# SCH_FinalThesis.net
KiCad netlist of a schematic drawn in EasyEDA
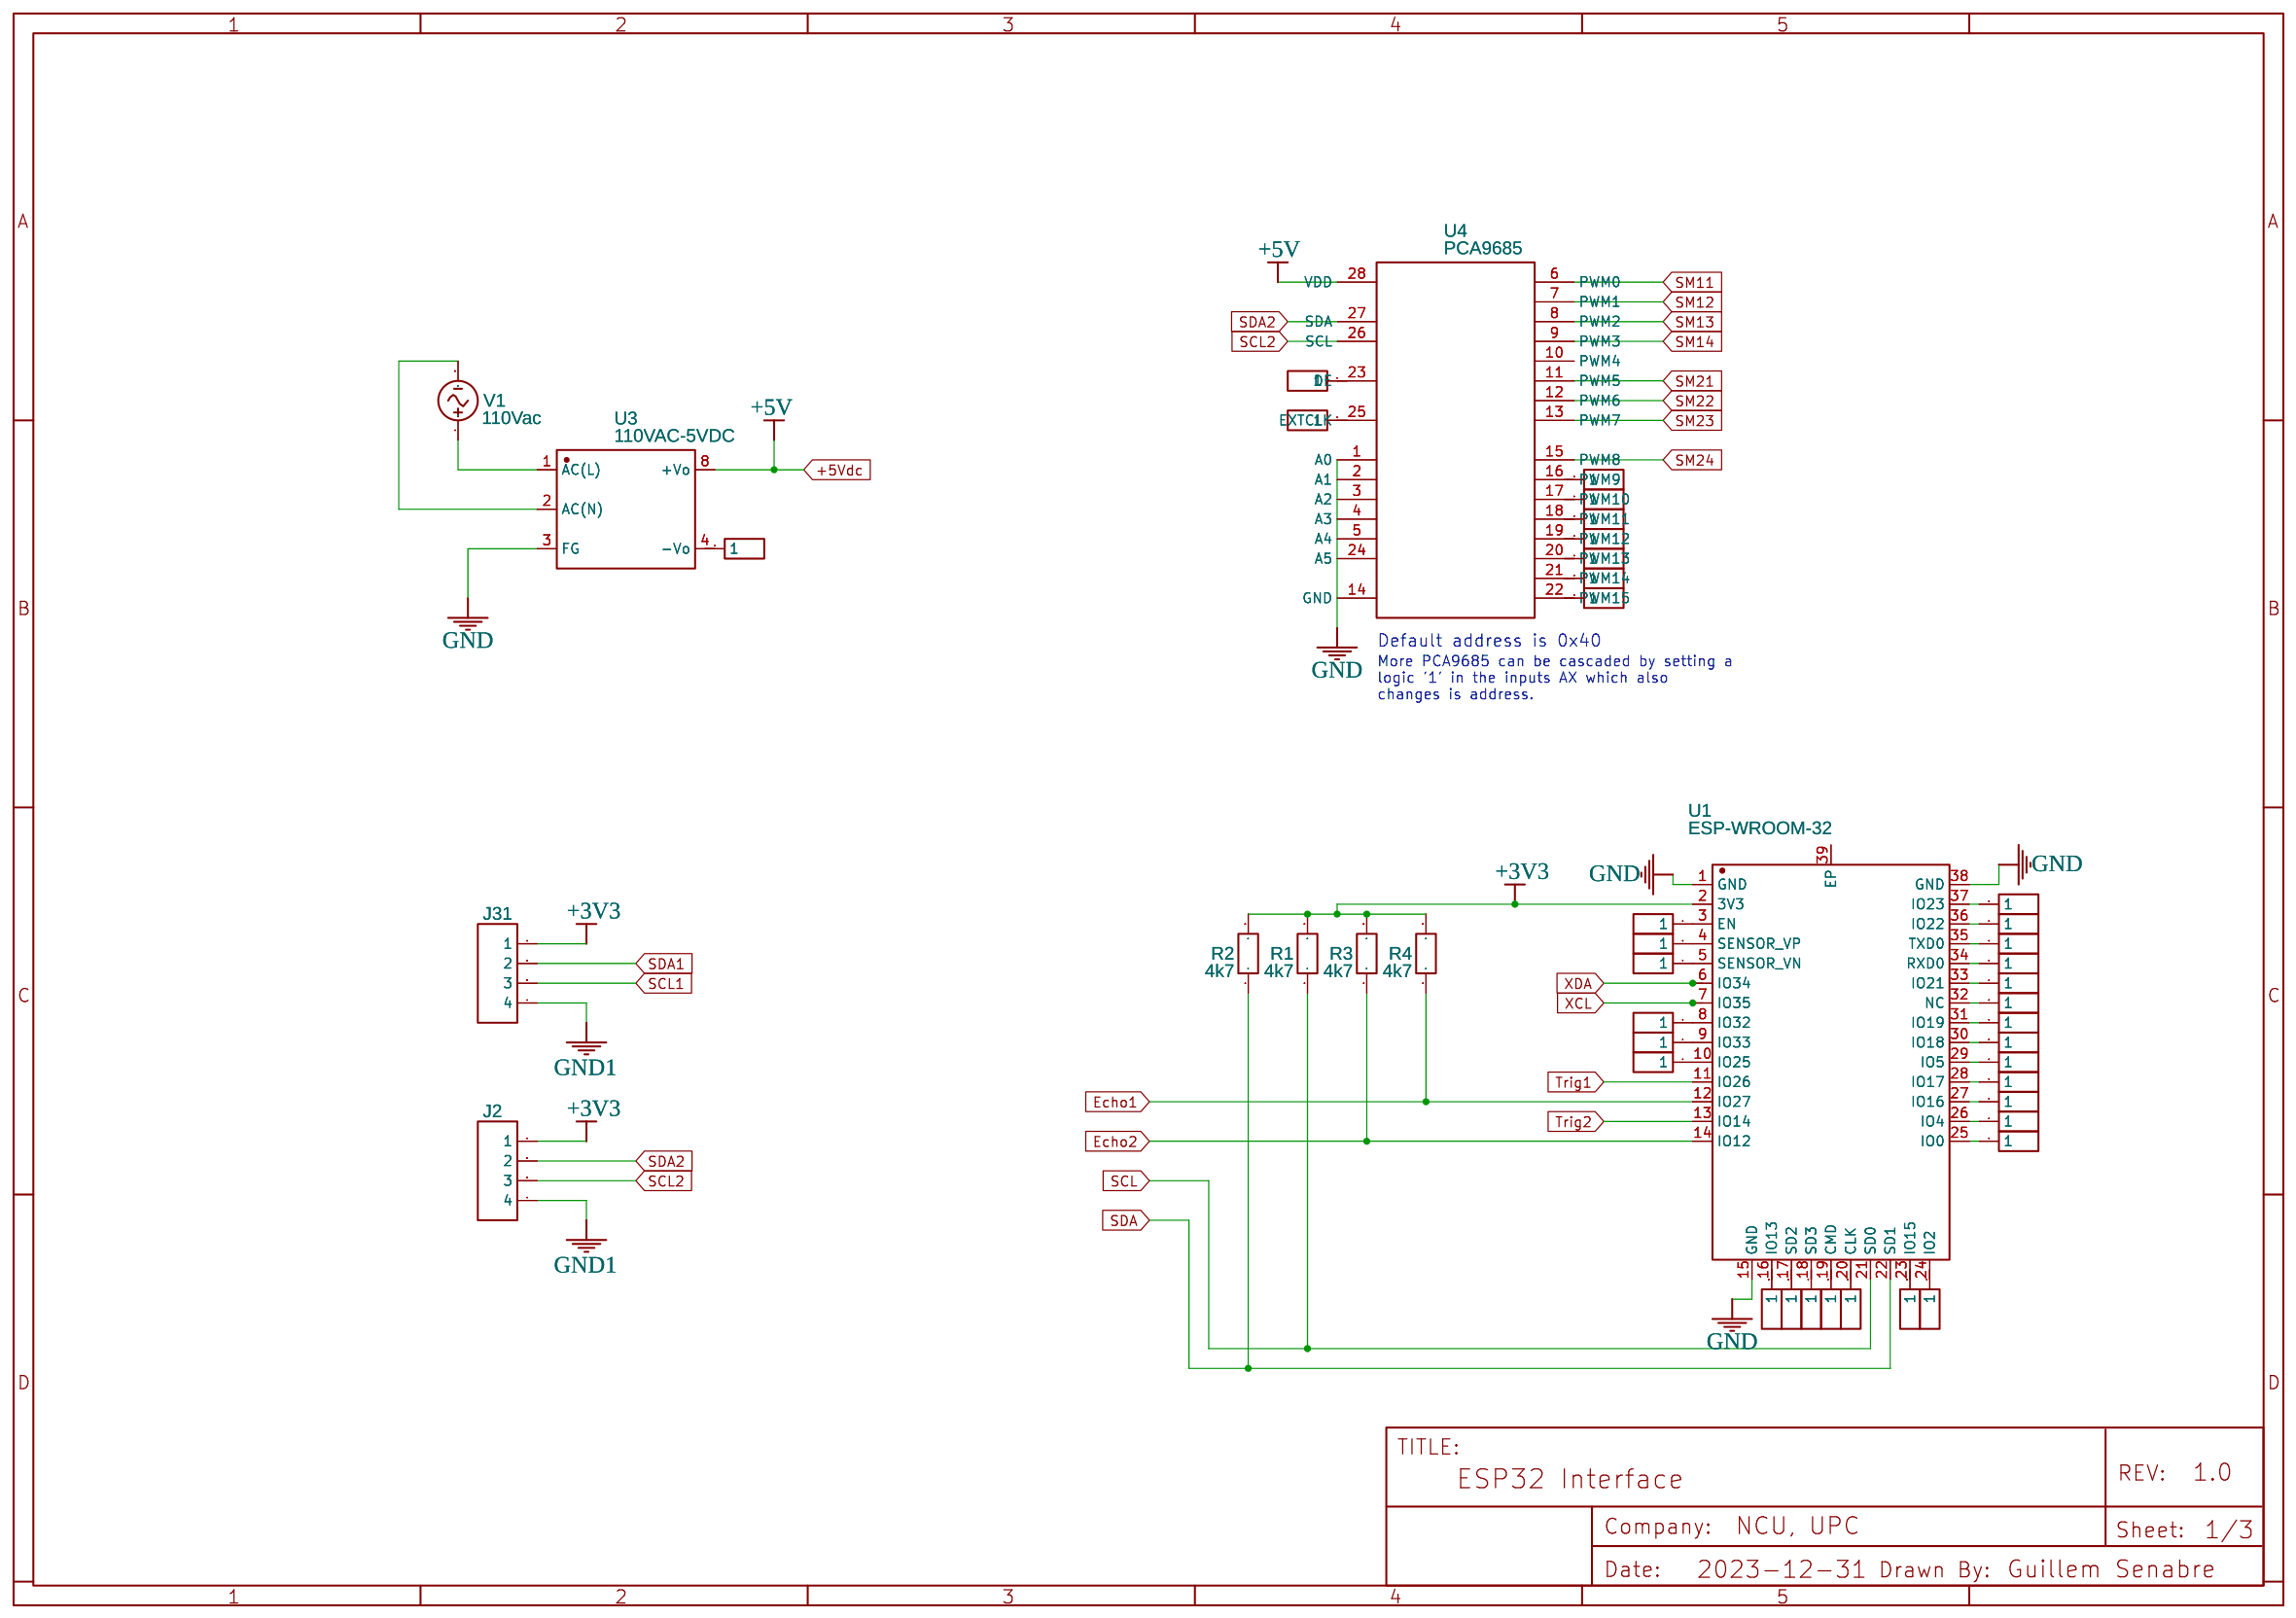
[diagram p0: Main]
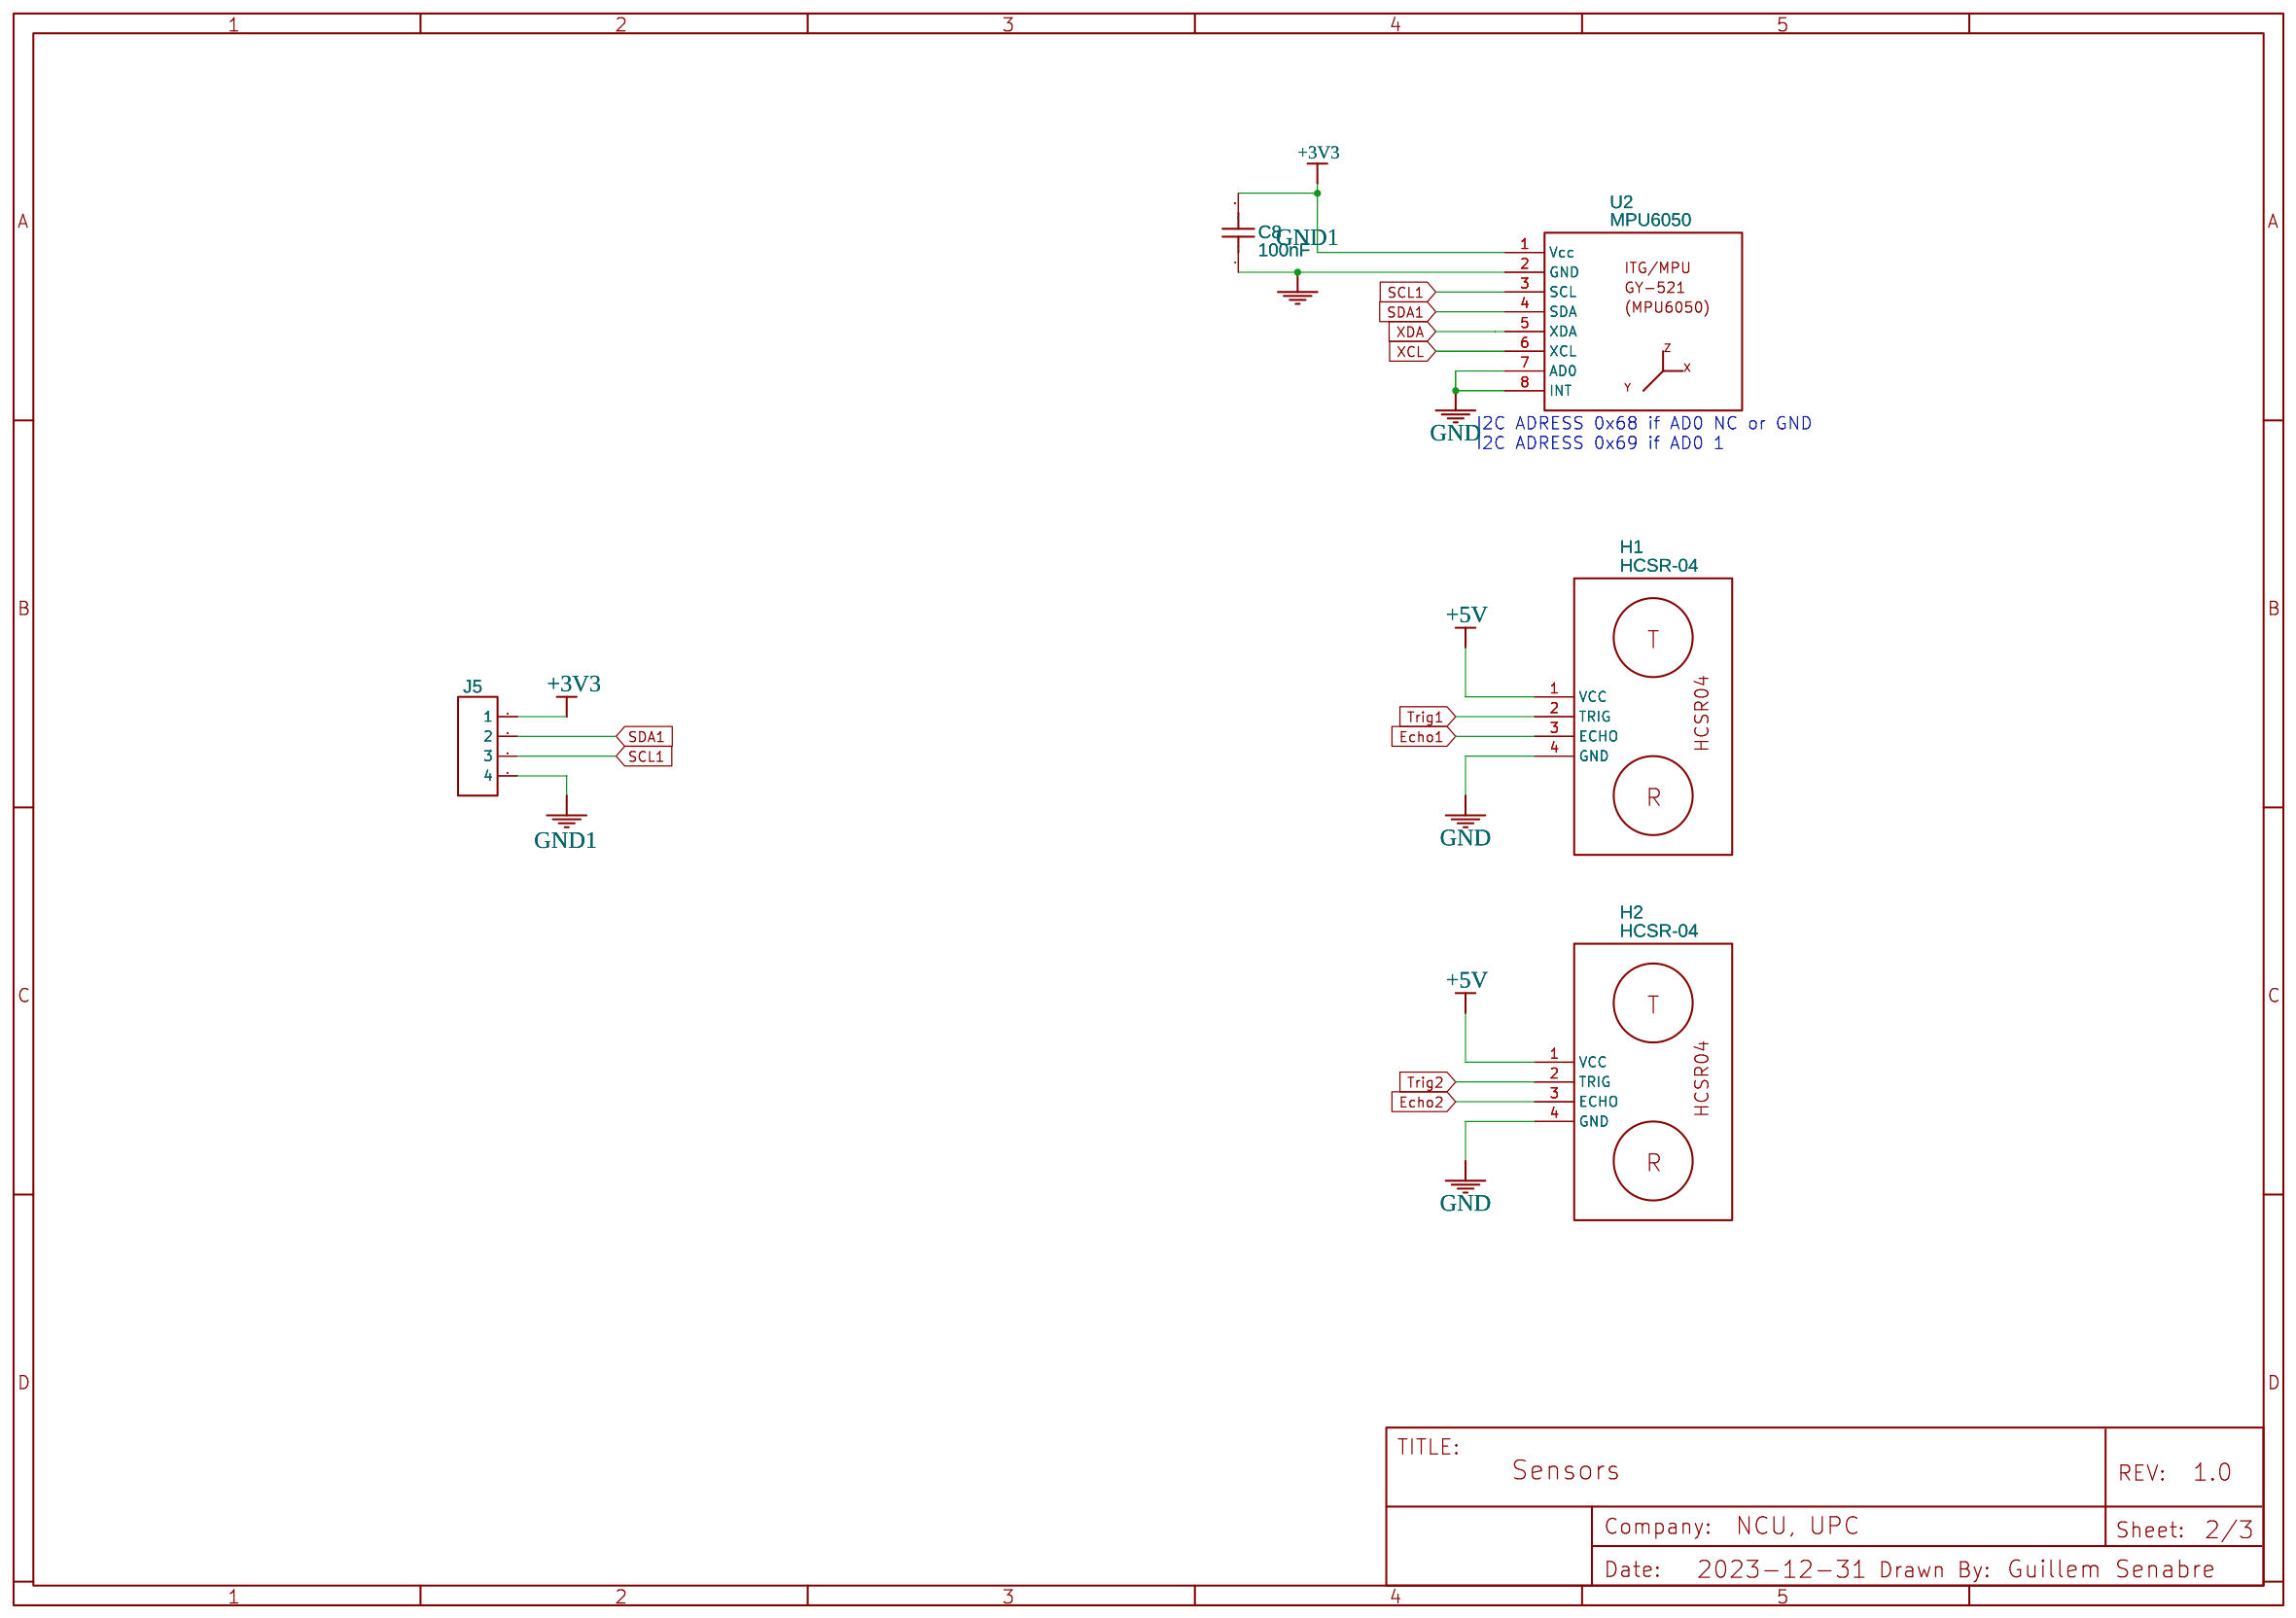
[diagram p1: Sensors]
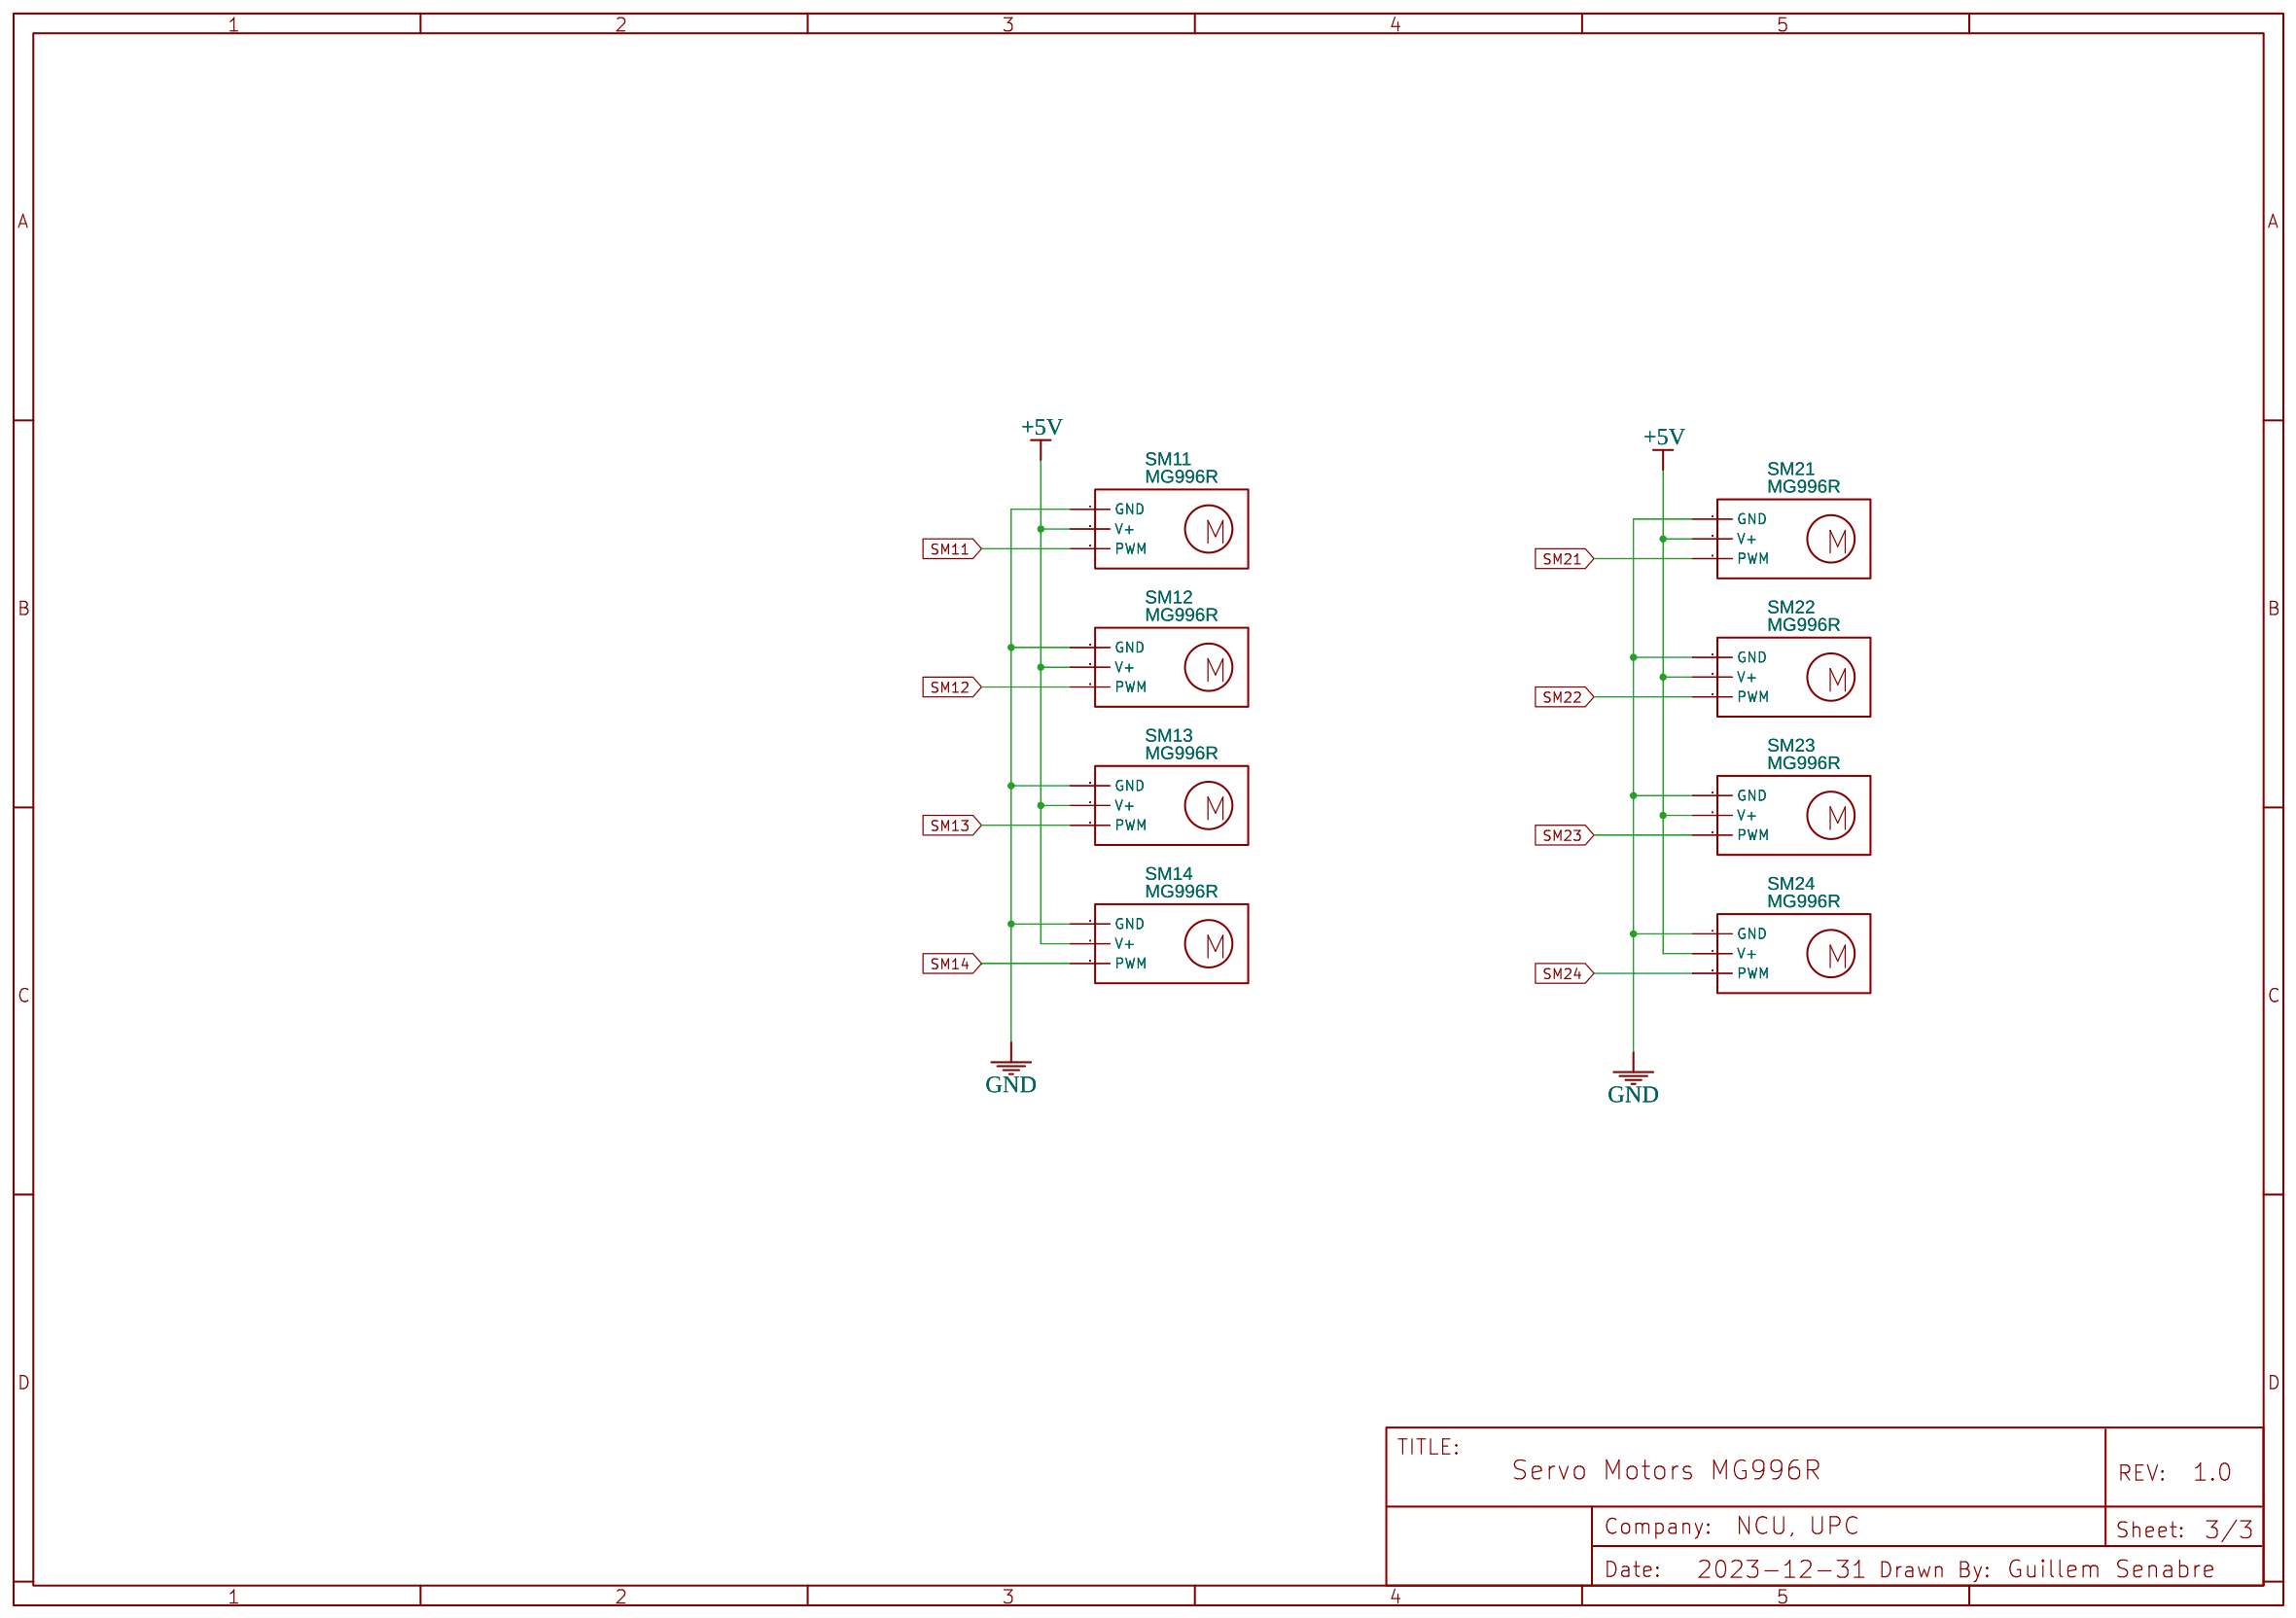
[diagram p2: Actuators]

(export (version "E")
  (design (tool "Eeschema 10.0.6"))
  (components
    (comp (ref "J1") (value "HDR-M-2.54_1x1") (libsource (lib "") (part "HDR-M-2.54_1x1_2")))
    (comp (ref "J2") (value "HDR-M-2.54_1x4") (libsource (lib "") (part "HDR-M-2.54_1x4")))
    (comp (ref "J3") (value "HDR-M-2.54_1x1") (libsource (lib "") (part "HDR-M-2.54_1x1_1")))
    (comp (ref "J4") (value "HDR-M-2.54_1x1") (libsource (lib "") (part "HDR-M-2.54_1x1_1")))
    (comp (ref "J6") (value "HDR-M-2.54_1x1") (libsource (lib "") (part "HDR-M-2.54_1x1_1")))
    (comp (ref "J7") (value "HDR-M-2.54_1x1") (libsource (lib "") (part "HDR-M-2.54_1x1_1")))
    (comp (ref "J8") (value "HDR-M-2.54_1x1") (libsource (lib "") (part "HDR-M-2.54_1x1_1")))
    (comp (ref "J9") (value "HDR-M-2.54_1x1") (libsource (lib "") (part "HDR-M-2.54_1x1_1")))
    (comp (ref "J10") (value "HDR-M-2.54_1x1") (libsource (lib "") (part "HDR-M-2.54_1x1")))
    (comp (ref "J11") (value "HDR-M-2.54_1x1") (libsource (lib "") (part "HDR-M-2.54_1x1")))
    (comp (ref "J12") (value "HDR-M-2.54_1x1") (libsource (lib "") (part "HDR-M-2.54_1x1")))
    (comp (ref "J13") (value "HDR-M-2.54_1x1") (libsource (lib "") (part "HDR-M-2.54_1x1")))
    (comp (ref "J14") (value "HDR-M-2.54_1x1") (libsource (lib "") (part "HDR-M-2.54_1x1")))
    (comp (ref "J15") (value "HDR-M-2.54_1x1") (libsource (lib "") (part "HDR-M-2.54_1x1")))
    (comp (ref "J16") (value "HDR-M-2.54_1x1") (libsource (lib "") (part "HDR-M-2.54_1x1")))
    (comp (ref "J17") (value "HDR-M-2.54_1x1") (libsource (lib "") (part "HDR-M-2.54_1x1")))
    (comp (ref "J18") (value "HDR-M-2.54_1x1") (libsource (lib "") (part "HDR-M-2.54_1x1")))
    (comp (ref "J20") (value "HDR-M-2.54_1x1") (libsource (lib "") (part "HDR-M-2.54_1x1_1")))
    (comp (ref "J21") (value "HDR-M-2.54_1x1") (libsource (lib "") (part "HDR-M-2.54_1x1_1")))
    (comp (ref "J23") (value "HDR-M-2.54_1x1") (libsource (lib "") (part "HDR-M-2.54_1x1")))
    (comp (ref "J24") (value "HDR-M-2.54_1x1") (libsource (lib "") (part "HDR-M-2.54_1x1")))
    (comp (ref "J25") (value "HDR-M-2.54_1x1") (libsource (lib "") (part "HDR-M-2.54_1x1")))
    (comp (ref "J26") (value "HDR-M-2.54_1x1") (libsource (lib "") (part "HDR-M-2.54_1x1")))
    (comp (ref "J27") (value "HDR-M-2.54_1x1") (libsource (lib "") (part "HDR-M-2.54_1x1")))
    (comp (ref "J28") (value "HDR-M-2.54_1x1") (libsource (lib "") (part "HDR-M-2.54_1x1_2")))
    (comp (ref "J29") (value "HDR-M-2.54_1x1") (libsource (lib "") (part "HDR-M-2.54_1x1_2")))
    (comp (ref "J30") (value "HDR-M-2.54_1x1") (libsource (lib "") (part "HDR-M-2.54_1x1_2")))
    (comp (ref "J31") (value "HDR-M-2.54_1x4") (libsource (lib "") (part "HDR-M-2.54_1x4")))
    (comp (ref "J32") (value "HDR-M-2.54_1x1") (libsource (lib "") (part "HDR-M-2.54_1x1")))
    (comp (ref "J33") (value "HDR-M-2.54_1x1") (libsource (lib "") (part "HDR-M-2.54_1x1")))
    (comp (ref "J34") (value "HDR-M-2.54_1x1") (libsource (lib "") (part "HDR-M-2.54_1x1")))
    (comp (ref "J35") (value "HDR-M-2.54_1x1") (libsource (lib "") (part "HDR-M-2.54_1x1")))
    (comp (ref "J36") (value "HDR-M-2.54_1x1") (libsource (lib "") (part "HDR-M-2.54_1x1")))
    (comp (ref "J37") (value "HDR-M-2.54_1x1") (libsource (lib "") (part "HDR-M-2.54_1x1")))
    (comp (ref "J38") (value "HDR-M-2.54_1x1") (libsource (lib "") (part "HDR-M-2.54_1x1")))
    (comp (ref "J39") (value "HDR-M-2.54_1x1") (libsource (lib "") (part "HDR-M-2.54_1x1_2")))
    (comp (ref "J40") (value "HDR-M-2.54_1x1") (libsource (lib "") (part "HDR-M-2.54_1x1_2")))
    (comp (ref "J42") (value "HDR-M-2.54_1x1") (libsource (lib "") (part "HDR-M-2.54_1x1_2")))
    (comp (ref "R1") (value "4k7") (libsource (lib "") (part "R_0603_EU")))
    (comp (ref "R2") (value "4k7") (libsource (lib "") (part "R_0603_EU")))
    (comp (ref "R3") (value "4k7") (libsource (lib "") (part "R_0603_EU")))
    (comp (ref "R4") (value "4k7") (libsource (lib "") (part "R_0603_EU")))
    (comp (ref "U1")
      (value "ESP-WROOM-32")
      (fields
        (field (name "Manufacturer Part") "ESP32-WROOM-32")
        (field (name "Manufacturer") "ESPRESSIF(乐鑫)")
      )
      (libsource (lib "") (part "ESP-WROOM-32"))
    )
    (comp (ref "U3")
      (value "110VAC-5VDC")
      (fields (field (name "Manufacturer Part") "ZY0JGB12CD-10W") (field (name "Manufacturer") "ZLG(致远电子)"))
      (libsource (lib "") (part "ZY0JGB12CD-10W"))
    )
    (comp (ref "U4")
      (value "PCA9685")
      (fields (field (name "Manufacturer") "NXP Semiconductors"))
      (libsource (lib "") (part "PCA9685"))
    )
    (comp (ref "V1") (value "110Vac") (libsource (lib "") (part "VSin")))
    (comp (ref "C8")
      (value "100nF")
      (fields (field (name "Manufacturer Part") "1206B104K500") (field (name "Manufacturer") "WTC"))
      (libsource (lib "") (part "1206B104K500"))
    )
    (comp (ref "H1") (value "HCSR-04") (libsource (lib "") (part "HCSR-04")))
    (comp (ref "H2") (value "HCSR-04") (libsource (lib "") (part "HCSR-04")))
    (comp (ref "J5") (value "HDR-M-2.54_1x4") (libsource (lib "") (part "HDR-M-2.54_1x4")))
    (comp (ref "U2") (value "MPU6050") (libsource (lib "") (part "GY-521")))
    (comp (ref "SM11")
      (value "MG996R")
      (fields (field (name "Manufacturer Part") "tawaninnovation"))
      (libsource (lib "") (part "MG996R"))
    )
    (comp (ref "SM12")
      (value "MG996R")
      (fields (field (name "Manufacturer Part") "tawaninnovation"))
      (libsource (lib "") (part "MG996R"))
    )
    (comp (ref "SM13")
      (value "MG996R")
      (fields (field (name "Manufacturer Part") "tawaninnovation"))
      (libsource (lib "") (part "MG996R"))
    )
    (comp (ref "SM14")
      (value "MG996R")
      (fields (field (name "Manufacturer Part") "tawaninnovation"))
      (libsource (lib "") (part "MG996R"))
    )
    (comp (ref "SM21")
      (value "MG996R")
      (fields (field (name "Manufacturer Part") "tawaninnovation"))
      (libsource (lib "") (part "MG996R"))
    )
    (comp (ref "SM22")
      (value "MG996R")
      (fields (field (name "Manufacturer Part") "tawaninnovation"))
      (libsource (lib "") (part "MG996R"))
    )
    (comp (ref "SM23")
      (value "MG996R")
      (fields (field (name "Manufacturer Part") "tawaninnovation"))
      (libsource (lib "") (part "MG996R"))
    )
    (comp (ref "SM24")
      (value "MG996R")
      (fields (field (name "Manufacturer Part") "tawaninnovation"))
      (libsource (lib "") (part "MG996R"))
    )
  )
  (nets
    (net (code "1") (name "+3V3") (class "Default")
      (node (ref "C8") (pin "2") (pinfunction "2_2") (pintype "unspecified"))
      (node (ref "J2") (pin "1") (pinfunction "1_1") (pintype "unspecified"))
      (node (ref "J31") (pin "1") (pinfunction "1_1") (pintype "unspecified"))
      (node (ref "J5") (pin "1") (pinfunction "1_1") (pintype "unspecified"))
      (node (ref "R1") (pin "2") (pinfunction "2_2") (pintype "unspecified"))
      (node (ref "R2") (pin "2") (pinfunction "2_2") (pintype "unspecified"))
      (node (ref "R3") (pin "2") (pinfunction "2_2") (pintype "unspecified"))
      (node (ref "R4") (pin "2") (pinfunction "2_2") (pintype "unspecified"))
      (node (ref "U1") (pin "2") (pinfunction "3V3_2") (pintype "unspecified"))
      (node (ref "U2") (pin "1") (pinfunction "Vcc_1") (pintype "unspecified"))
    )
    (net (code "2") (name "+5Vdc") (class "Default")
      (node (ref "H1") (pin "1") (pinfunction "VCC_1") (pintype "unspecified"))
      (node (ref "H2") (pin "1") (pinfunction "VCC_1") (pintype "unspecified"))
      (node (ref "SM11") (pin "2") (pinfunction "V+_2") (pintype "unspecified"))
      (node (ref "SM12") (pin "2") (pinfunction "V+_2") (pintype "unspecified"))
      (node (ref "SM13") (pin "2") (pinfunction "V+_2") (pintype "unspecified"))
      (node (ref "SM14") (pin "2") (pinfunction "V+_2") (pintype "unspecified"))
      (node (ref "SM21") (pin "2") (pinfunction "V+_2") (pintype "unspecified"))
      (node (ref "SM22") (pin "2") (pinfunction "V+_2") (pintype "unspecified"))
      (node (ref "SM23") (pin "2") (pinfunction "V+_2") (pintype "unspecified"))
      (node (ref "SM24") (pin "2") (pinfunction "V+_2") (pintype "unspecified"))
      (node (ref "U3") (pin "8") (pinfunction "+Vo_8") (pintype "unspecified"))
    )
    (net (code "3") (name "Echo1") (class "Default")
      (node (ref "H1") (pin "3") (pinfunction "ECHO_3") (pintype "unspecified"))
      (node (ref "R4") (pin "1") (pinfunction "1_1") (pintype "unspecified"))
      (node (ref "U1") (pin "12") (pinfunction "IO27_12") (pintype "unspecified"))
    )
    (net (code "4") (name "Echo2") (class "Default")
      (node (ref "H2") (pin "3") (pinfunction "ECHO_3") (pintype "unspecified"))
      (node (ref "R3") (pin "1") (pinfunction "1_1") (pintype "unspecified"))
      (node (ref "U1") (pin "14") (pinfunction "IO12_14") (pintype "unspecified"))
    )
    (net (code "5") (name "GND") (class "Default")
      (node (ref "H1") (pin "4") (pinfunction "GND_4") (pintype "unspecified"))
      (node (ref "H2") (pin "4") (pinfunction "GND_4") (pintype "unspecified"))
      (node (ref "SM11") (pin "1") (pinfunction "GND_1") (pintype "unspecified"))
      (node (ref "SM12") (pin "1") (pinfunction "GND_1") (pintype "unspecified"))
      (node (ref "SM13") (pin "1") (pinfunction "GND_1") (pintype "unspecified"))
      (node (ref "SM14") (pin "1") (pinfunction "GND_1") (pintype "unspecified"))
      (node (ref "SM21") (pin "1") (pinfunction "GND_1") (pintype "unspecified"))
      (node (ref "SM22") (pin "1") (pinfunction "GND_1") (pintype "unspecified"))
      (node (ref "SM23") (pin "1") (pinfunction "GND_1") (pintype "unspecified"))
      (node (ref "SM24") (pin "1") (pinfunction "GND_1") (pintype "unspecified"))
      (node (ref "U1") (pin "1") (pinfunction "GND_1") (pintype "unspecified"))
      (node (ref "U1") (pin "15") (pinfunction "GND_15") (pintype "unspecified"))
      (node (ref "U1") (pin "38") (pinfunction "GND_38") (pintype "unspecified"))
      (node (ref "U2") (pin "7") (pinfunction "AD0_7") (pintype "unspecified"))
      (node (ref "U2") (pin "8") (pinfunction "INT_8") (pintype "unspecified"))
      (node (ref "U3") (pin "3") (pinfunction "FG_3") (pintype "unspecified"))
    )
    (net (code "6") (name "GND1") (class "Default")
      (node (ref "C8") (pin "1") (pinfunction "1_1") (pintype "unspecified"))
      (node (ref "J2") (pin "4") (pinfunction "4_4") (pintype "unspecified"))
      (node (ref "J31") (pin "4") (pinfunction "4_4") (pintype "unspecified"))
      (node (ref "J5") (pin "4") (pinfunction "4_4") (pintype "unspecified"))
      (node (ref "U2") (pin "2") (pinfunction "GND_2") (pintype "unspecified"))
    )
    (net (code "7") (name "Net-(U1-CLK)") (class "Default")
      (node (ref "J40") (pin "1") (pinfunction "1_1") (pintype "input"))
      (node (ref "U1") (pin "20") (pinfunction "CLK_20") (pintype "unspecified"))
    )
    (net (code "8") (name "Net-(U1-CMD)") (class "Default")
      (node (ref "J29") (pin "1") (pinfunction "1_1") (pintype "input"))
      (node (ref "U1") (pin "19") (pinfunction "CMD_19") (pintype "unspecified"))
    )
    (net (code "9") (name "Net-(U1-EN)") (class "Default")
      (node (ref "J3") (pin "1") (pinfunction "1_1") (pintype "input"))
      (node (ref "U1") (pin "3") (pinfunction "EN_3") (pintype "unspecified"))
    )
    (net (code "10") (name "Net-(U1-IO0)") (class "Default")
      (node (ref "J27") (pin "1") (pinfunction "1_1") (pintype "input"))
      (node (ref "U1") (pin "25") (pinfunction "IO0_25") (pintype "unspecified"))
    )
    (net (code "11") (name "Net-(U1-IO2)") (class "Default")
      (node (ref "J42") (pin "1") (pinfunction "1_1") (pintype "input"))
      (node (ref "U1") (pin "24") (pinfunction "IO2_24") (pintype "unspecified"))
    )
    (net (code "12") (name "Net-(U1-IO4)") (class "Default")
      (node (ref "J23") (pin "1") (pinfunction "1_1") (pintype "input"))
      (node (ref "U1") (pin "26") (pinfunction "IO4_26") (pintype "unspecified"))
    )
    (net (code "13") (name "Net-(U1-IO5)") (class "Default")
      (node (ref "J25") (pin "1") (pinfunction "1_1") (pintype "input"))
      (node (ref "U1") (pin "29") (pinfunction "IO5_29") (pintype "unspecified"))
    )
    (net (code "14") (name "Net-(U1-IO13)") (class "Default")
      (node (ref "J39") (pin "1") (pinfunction "1_1") (pintype "input"))
      (node (ref "U1") (pin "16") (pinfunction "IO13_16") (pintype "unspecified"))
    )
    (net (code "15") (name "Net-(U1-IO15)") (class "Default")
      (node (ref "J1") (pin "1") (pinfunction "1_1") (pintype "input"))
      (node (ref "U1") (pin "23") (pinfunction "IO15_23") (pintype "unspecified"))
    )
    (net (code "16") (name "Net-(U1-IO16)") (class "Default")
      (node (ref "J24") (pin "1") (pinfunction "1_1") (pintype "input"))
      (node (ref "U1") (pin "27") (pinfunction "IO16_27") (pintype "unspecified"))
    )
    (net (code "17") (name "Net-(U1-IO17)") (class "Default")
      (node (ref "J26") (pin "1") (pinfunction "1_1") (pintype "input"))
      (node (ref "U1") (pin "28") (pinfunction "IO17_28") (pintype "unspecified"))
    )
    (net (code "18") (name "Net-(U1-IO18)") (class "Default")
      (node (ref "J18") (pin "1") (pinfunction "1_1") (pintype "input"))
      (node (ref "U1") (pin "30") (pinfunction "IO18_30") (pintype "unspecified"))
    )
    (net (code "19") (name "Net-(U1-IO19)") (class "Default")
      (node (ref "J17") (pin "1") (pinfunction "1_1") (pintype "input"))
      (node (ref "U1") (pin "31") (pinfunction "IO19_31") (pintype "unspecified"))
    )
    (net (code "20") (name "Net-(U1-IO21)") (class "Default")
      (node (ref "J16") (pin "1") (pinfunction "1_1") (pintype "input"))
      (node (ref "U1") (pin "33") (pinfunction "IO21_33") (pintype "unspecified"))
    )
    (net (code "21") (name "Net-(U1-IO22)") (class "Default")
      (node (ref "J14") (pin "1") (pinfunction "1_1") (pintype "input"))
      (node (ref "U1") (pin "36") (pinfunction "IO22_36") (pintype "unspecified"))
    )
    (net (code "22") (name "Net-(U1-IO23)") (class "Default")
      (node (ref "J13") (pin "1") (pinfunction "1_1") (pintype "input"))
      (node (ref "U1") (pin "37") (pinfunction "IO23_37") (pintype "unspecified"))
    )
    (net (code "23") (name "Net-(U1-IO25)") (class "Default")
      (node (ref "J8") (pin "1") (pinfunction "1_1") (pintype "input"))
      (node (ref "U1") (pin "10") (pinfunction "IO25_10") (pintype "unspecified"))
    )
    (net (code "24") (name "Net-(U1-IO32)") (class "Default")
      (node (ref "J9") (pin "1") (pinfunction "1_1") (pintype "input"))
      (node (ref "U1") (pin "8") (pinfunction "IO32_8") (pintype "unspecified"))
    )
    (net (code "25") (name "Net-(U1-IO33)") (class "Default")
      (node (ref "J7") (pin "1") (pinfunction "1_1") (pintype "input"))
      (node (ref "U1") (pin "9") (pinfunction "IO33_9") (pintype "unspecified"))
    )
    (net (code "26") (name "Net-(U1-NC)") (class "Default")
      (node (ref "J15") (pin "1") (pinfunction "1_1") (pintype "input"))
      (node (ref "U1") (pin "32") (pinfunction "NC_32") (pintype "unspecified"))
    )
    (net (code "27") (name "Net-(U1-RXD0)") (class "Default")
      (node (ref "J11") (pin "1") (pinfunction "1_1") (pintype "input"))
      (node (ref "U1") (pin "34") (pinfunction "RXD0_34") (pintype "unspecified"))
    )
    (net (code "28") (name "Net-(U1-SD2)") (class "Default")
      (node (ref "J30") (pin "1") (pinfunction "1_1") (pintype "input"))
      (node (ref "U1") (pin "17") (pinfunction "SD2_17") (pintype "unspecified"))
    )
    (net (code "29") (name "Net-(U1-SD3)") (class "Default")
      (node (ref "J28") (pin "1") (pinfunction "1_1") (pintype "input"))
      (node (ref "U1") (pin "18") (pinfunction "SD3_18") (pintype "unspecified"))
    )
    (net (code "30") (name "Net-(U1-SENSOR_VN)") (class "Default")
      (node (ref "J6") (pin "1") (pinfunction "1_1") (pintype "input"))
      (node (ref "U1") (pin "5") (pinfunction "SENSOR_VN_5") (pintype "unspecified"))
    )
    (net (code "31") (name "Net-(U1-SENSOR_VP)") (class "Default")
      (node (ref "J4") (pin "1") (pinfunction "1_1") (pintype "input"))
      (node (ref "U1") (pin "4") (pinfunction "SENSOR_VP_4") (pintype "unspecified"))
    )
    (net (code "32") (name "Net-(U1-TXD0)") (class "Default")
      (node (ref "J12") (pin "1") (pinfunction "1_1") (pintype "input"))
      (node (ref "U1") (pin "35") (pinfunction "TXD0_35") (pintype "unspecified"))
    )
    (net (code "33") (name "Net-(U3--Vo)") (class "Default")
      (node (ref "J10") (pin "1") (pinfunction "1_1") (pintype "input"))
      (node (ref "U3") (pin "4") (pinfunction "-Vo_4") (pintype "unspecified"))
    )
    (net (code "34") (name "Net-(U3-AC(L))") (class "Default")
      (node (ref "U3") (pin "1") (pinfunction "AC(L)_1") (pintype "unspecified"))
      (node (ref "V1") (pin "1") (pinfunction "1_1") (pintype "unspecified"))
    )
    (net (code "35") (name "Net-(U3-AC(N))") (class "Default")
      (node (ref "U3") (pin "2") (pinfunction "AC(N)_2") (pintype "unspecified"))
      (node (ref "V1") (pin "2") (pinfunction "2_2") (pintype "unspecified"))
    )
    (net (code "36") (name "SCL") (class "Default")
      (node (ref "R1") (pin "1") (pinfunction "1_1") (pintype "unspecified"))
      (node (ref "U1") (pin "21") (pinfunction "SD0_21") (pintype "unspecified"))
    )
    (net (code "37") (name "SCL1") (class "Default")
      (node (ref "J31") (pin "3") (pinfunction "3_3") (pintype "unspecified"))
      (node (ref "J5") (pin "3") (pinfunction "3_3") (pintype "unspecified"))
      (node (ref "U2") (pin "3") (pinfunction "SCL_3") (pintype "unspecified"))
    )
    (net (code "38") (name "SCL2") (class "Default")
      (node (ref "J2") (pin "3") (pinfunction "3_3") (pintype "unspecified"))
    )
    (net (code "39") (name "SDA") (class "Default")
      (node (ref "R2") (pin "1") (pinfunction "1_1") (pintype "unspecified"))
      (node (ref "U1") (pin "22") (pinfunction "SD1_22") (pintype "unspecified"))
    )
    (net (code "40") (name "SDA1") (class "Default")
      (node (ref "J31") (pin "2") (pinfunction "2_2") (pintype "unspecified"))
      (node (ref "J5") (pin "2") (pinfunction "2_2") (pintype "unspecified"))
      (node (ref "U2") (pin "4") (pinfunction "SDA_4") (pintype "unspecified"))
    )
    (net (code "41") (name "SDA2") (class "Default")
      (node (ref "J2") (pin "2") (pinfunction "2_2") (pintype "unspecified"))
    )
    (net (code "42") (name "SM11") (class "Default")
      (node (ref "SM11") (pin "3") (pinfunction "PWM_3") (pintype "unspecified"))
    )
    (net (code "43") (name "SM12") (class "Default")
      (node (ref "SM12") (pin "3") (pinfunction "PWM_3") (pintype "unspecified"))
    )
    (net (code "44") (name "SM13") (class "Default")
      (node (ref "SM13") (pin "3") (pinfunction "PWM_3") (pintype "unspecified"))
    )
    (net (code "45") (name "SM14") (class "Default")
      (node (ref "SM14") (pin "3") (pinfunction "PWM_3") (pintype "unspecified"))
    )
    (net (code "46") (name "SM21") (class "Default")
      (node (ref "SM21") (pin "3") (pinfunction "PWM_3") (pintype "unspecified"))
    )
    (net (code "47") (name "SM22") (class "Default")
      (node (ref "SM22") (pin "3") (pinfunction "PWM_3") (pintype "unspecified"))
    )
    (net (code "48") (name "SM23") (class "Default")
      (node (ref "SM23") (pin "3") (pinfunction "PWM_3") (pintype "unspecified"))
    )
    (net (code "49") (name "SM24") (class "Default")
      (node (ref "SM24") (pin "3") (pinfunction "PWM_3") (pintype "unspecified"))
    )
    (net (code "50") (name "Trig1") (class "Default")
      (node (ref "H1") (pin "2") (pinfunction "TRIG_2") (pintype "unspecified"))
      (node (ref "U1") (pin "11") (pinfunction "IO26_11") (pintype "unspecified"))
    )
    (net (code "51") (name "Trig2") (class "Default")
      (node (ref "H2") (pin "2") (pinfunction "TRIG_2") (pintype "unspecified"))
      (node (ref "U1") (pin "13") (pinfunction "IO14_13") (pintype "unspecified"))
    )
    (net (code "52") (name "XCL") (class "Default")
      (node (ref "U1") (pin "7") (pinfunction "IO35_7") (pintype "unspecified"))
      (node (ref "U2") (pin "6") (pinfunction "XCL_6") (pintype "unspecified"))
    )
    (net (code "53") (name "XDA") (class "Default")
      (node (ref "U1") (pin "6") (pinfunction "IO34_6") (pintype "unspecified"))
      (node (ref "U2") (pin "5") (pinfunction "XDA_5") (pintype "unspecified"))
    )
    (net (code "54") (name "unconnected-(J20-Pad1)") (class "Default")
      (node (ref "J20") (pin "1") (pinfunction "1_1") (pintype "input"))
    )
    (net (code "55") (name "unconnected-(J21-Pad1)") (class "Default")
      (node (ref "J21") (pin "1") (pinfunction "1_1") (pintype "input"))
    )
    (net (code "56") (name "unconnected-(J32-Pad1)") (class "Default")
      (node (ref "J32") (pin "1") (pinfunction "1_1") (pintype "input"))
    )
    (net (code "57") (name "unconnected-(J33-Pad1)") (class "Default")
      (node (ref "J33") (pin "1") (pinfunction "1_1") (pintype "input"))
    )
    (net (code "58") (name "unconnected-(J34-Pad1)") (class "Default")
      (node (ref "J34") (pin "1") (pinfunction "1_1") (pintype "input"))
    )
    (net (code "59") (name "unconnected-(J35-Pad1)") (class "Default")
      (node (ref "J35") (pin "1") (pinfunction "1_1") (pintype "input"))
    )
    (net (code "60") (name "unconnected-(J36-Pad1)") (class "Default")
      (node (ref "J36") (pin "1") (pinfunction "1_1") (pintype "input"))
    )
    (net (code "61") (name "unconnected-(J37-Pad1)") (class "Default")
      (node (ref "J37") (pin "1") (pinfunction "1_1") (pintype "input"))
    )
    (net (code "62") (name "unconnected-(J38-Pad1)") (class "Default")
      (node (ref "J38") (pin "1") (pinfunction "1_1") (pintype "input"))
    )
    (net (code "63") (name "unconnected-(U1-EP-Pad39)") (class "Default")
      (node (ref "U1") (pin "39") (pinfunction "EP_39") (pintype "unspecified"))
    )
    (net (code "64") (name "unconnected-(U4-A0-Pad1)") (class "Default")
      (node (ref "U4") (pin "1") (pinfunction "A0_1") (pintype "unspecified"))
    )
    (net (code "65") (name "unconnected-(U4-A1-Pad2)") (class "Default")
      (node (ref "U4") (pin "2") (pinfunction "A1_2") (pintype "unspecified"))
    )
    (net (code "66") (name "unconnected-(U4-A2-Pad3)") (class "Default")
      (node (ref "U4") (pin "3") (pinfunction "A2_3") (pintype "unspecified"))
    )
    (net (code "67") (name "unconnected-(U4-A3-Pad4)") (class "Default")
      (node (ref "U4") (pin "4") (pinfunction "A3_4") (pintype "unspecified"))
    )
    (net (code "68") (name "unconnected-(U4-A4-Pad5)") (class "Default")
      (node (ref "U4") (pin "5") (pinfunction "A4_5") (pintype "unspecified"))
    )
    (net (code "69") (name "unconnected-(U4-A5-Pad24)") (class "Default")
      (node (ref "U4") (pin "24") (pinfunction "A5_24") (pintype "unspecified"))
    )
    (net (code "70") (name "unconnected-(U4-DE-Pad23)") (class "Default")
      (node (ref "U4") (pin "23") (pinfunction "DE_23") (pintype "unspecified"))
    )
    (net (code "71") (name "unconnected-(U4-EXTCLK-Pad25)") (class "Default")
      (node (ref "U4") (pin "25") (pinfunction "EXTCLK_25") (pintype "unspecified"))
    )
    (net (code "72") (name "unconnected-(U4-GND-Pad14)") (class "Default")
      (node (ref "U4") (pin "14") (pinfunction "GND_14") (pintype "unspecified"))
    )
    (net (code "73") (name "unconnected-(U4-PWM0-Pad6)") (class "Default")
      (node (ref "U4") (pin "6") (pinfunction "PWM0_6") (pintype "unspecified"))
    )
    (net (code "74") (name "unconnected-(U4-PWM1-Pad7)") (class "Default")
      (node (ref "U4") (pin "7") (pinfunction "PWM1_7") (pintype "unspecified"))
    )
    (net (code "75") (name "unconnected-(U4-PWM2-Pad8)") (class "Default")
      (node (ref "U4") (pin "8") (pinfunction "PWM2_8") (pintype "unspecified"))
    )
    (net (code "76") (name "unconnected-(U4-PWM3-Pad9)") (class "Default")
      (node (ref "U4") (pin "9") (pinfunction "PWM3_9") (pintype "unspecified"))
    )
    (net (code "77") (name "unconnected-(U4-PWM4-Pad10)") (class "Default")
      (node (ref "U4") (pin "10") (pinfunction "PWM4_10") (pintype "unspecified"))
    )
    (net (code "78") (name "unconnected-(U4-PWM5-Pad11)") (class "Default")
      (node (ref "U4") (pin "11") (pinfunction "PWM5_11") (pintype "unspecified"))
    )
    (net (code "79") (name "unconnected-(U4-PWM6-Pad12)") (class "Default")
      (node (ref "U4") (pin "12") (pinfunction "PWM6_12") (pintype "unspecified"))
    )
    (net (code "80") (name "unconnected-(U4-PWM7-Pad13)") (class "Default")
      (node (ref "U4") (pin "13") (pinfunction "PWM7_13") (pintype "unspecified"))
    )
    (net (code "81") (name "unconnected-(U4-PWM8-Pad15)") (class "Default")
      (node (ref "U4") (pin "15") (pinfunction "PWM8_15") (pintype "unspecified"))
    )
    (net (code "82") (name "unconnected-(U4-PWM9-Pad16)") (class "Default")
      (node (ref "U4") (pin "16") (pinfunction "PWM9_16") (pintype "unspecified"))
    )
    (net (code "83") (name "unconnected-(U4-PWM10-Pad17)") (class "Default")
      (node (ref "U4") (pin "17") (pinfunction "PWM10_17") (pintype "unspecified"))
    )
    (net (code "84") (name "unconnected-(U4-PWM11-Pad18)") (class "Default")
      (node (ref "U4") (pin "18") (pinfunction "PWM11_18") (pintype "unspecified"))
    )
    (net (code "85") (name "unconnected-(U4-PWM12-Pad19)") (class "Default")
      (node (ref "U4") (pin "19") (pinfunction "PWM12_19") (pintype "unspecified"))
    )
    (net (code "86") (name "unconnected-(U4-PWM13-Pad20)") (class "Default")
      (node (ref "U4") (pin "20") (pinfunction "PWM13_20") (pintype "unspecified"))
    )
    (net (code "87") (name "unconnected-(U4-PWM14-Pad21)") (class "Default")
      (node (ref "U4") (pin "21") (pinfunction "PWM14_21") (pintype "unspecified"))
    )
    (net (code "88") (name "unconnected-(U4-PWM15-Pad22)") (class "Default")
      (node (ref "U4") (pin "22") (pinfunction "PWM15_22") (pintype "unspecified"))
    )
    (net (code "89") (name "unconnected-(U4-SCL-Pad26)") (class "Default")
      (node (ref "U4") (pin "26") (pinfunction "SCL_26") (pintype "unspecified"))
    )
    (net (code "90") (name "unconnected-(U4-SDA-Pad27)") (class "Default")
      (node (ref "U4") (pin "27") (pinfunction "SDA_27") (pintype "unspecified"))
    )
    (net (code "91") (name "unconnected-(U4-VDD-Pad28)") (class "Default")
      (node (ref "U4") (pin "28") (pinfunction "VDD_28") (pintype "unspecified"))
    )
  )
)
